# hand_rev_1_0.net
KiCad netlist of a schematic drawn in EAGLE
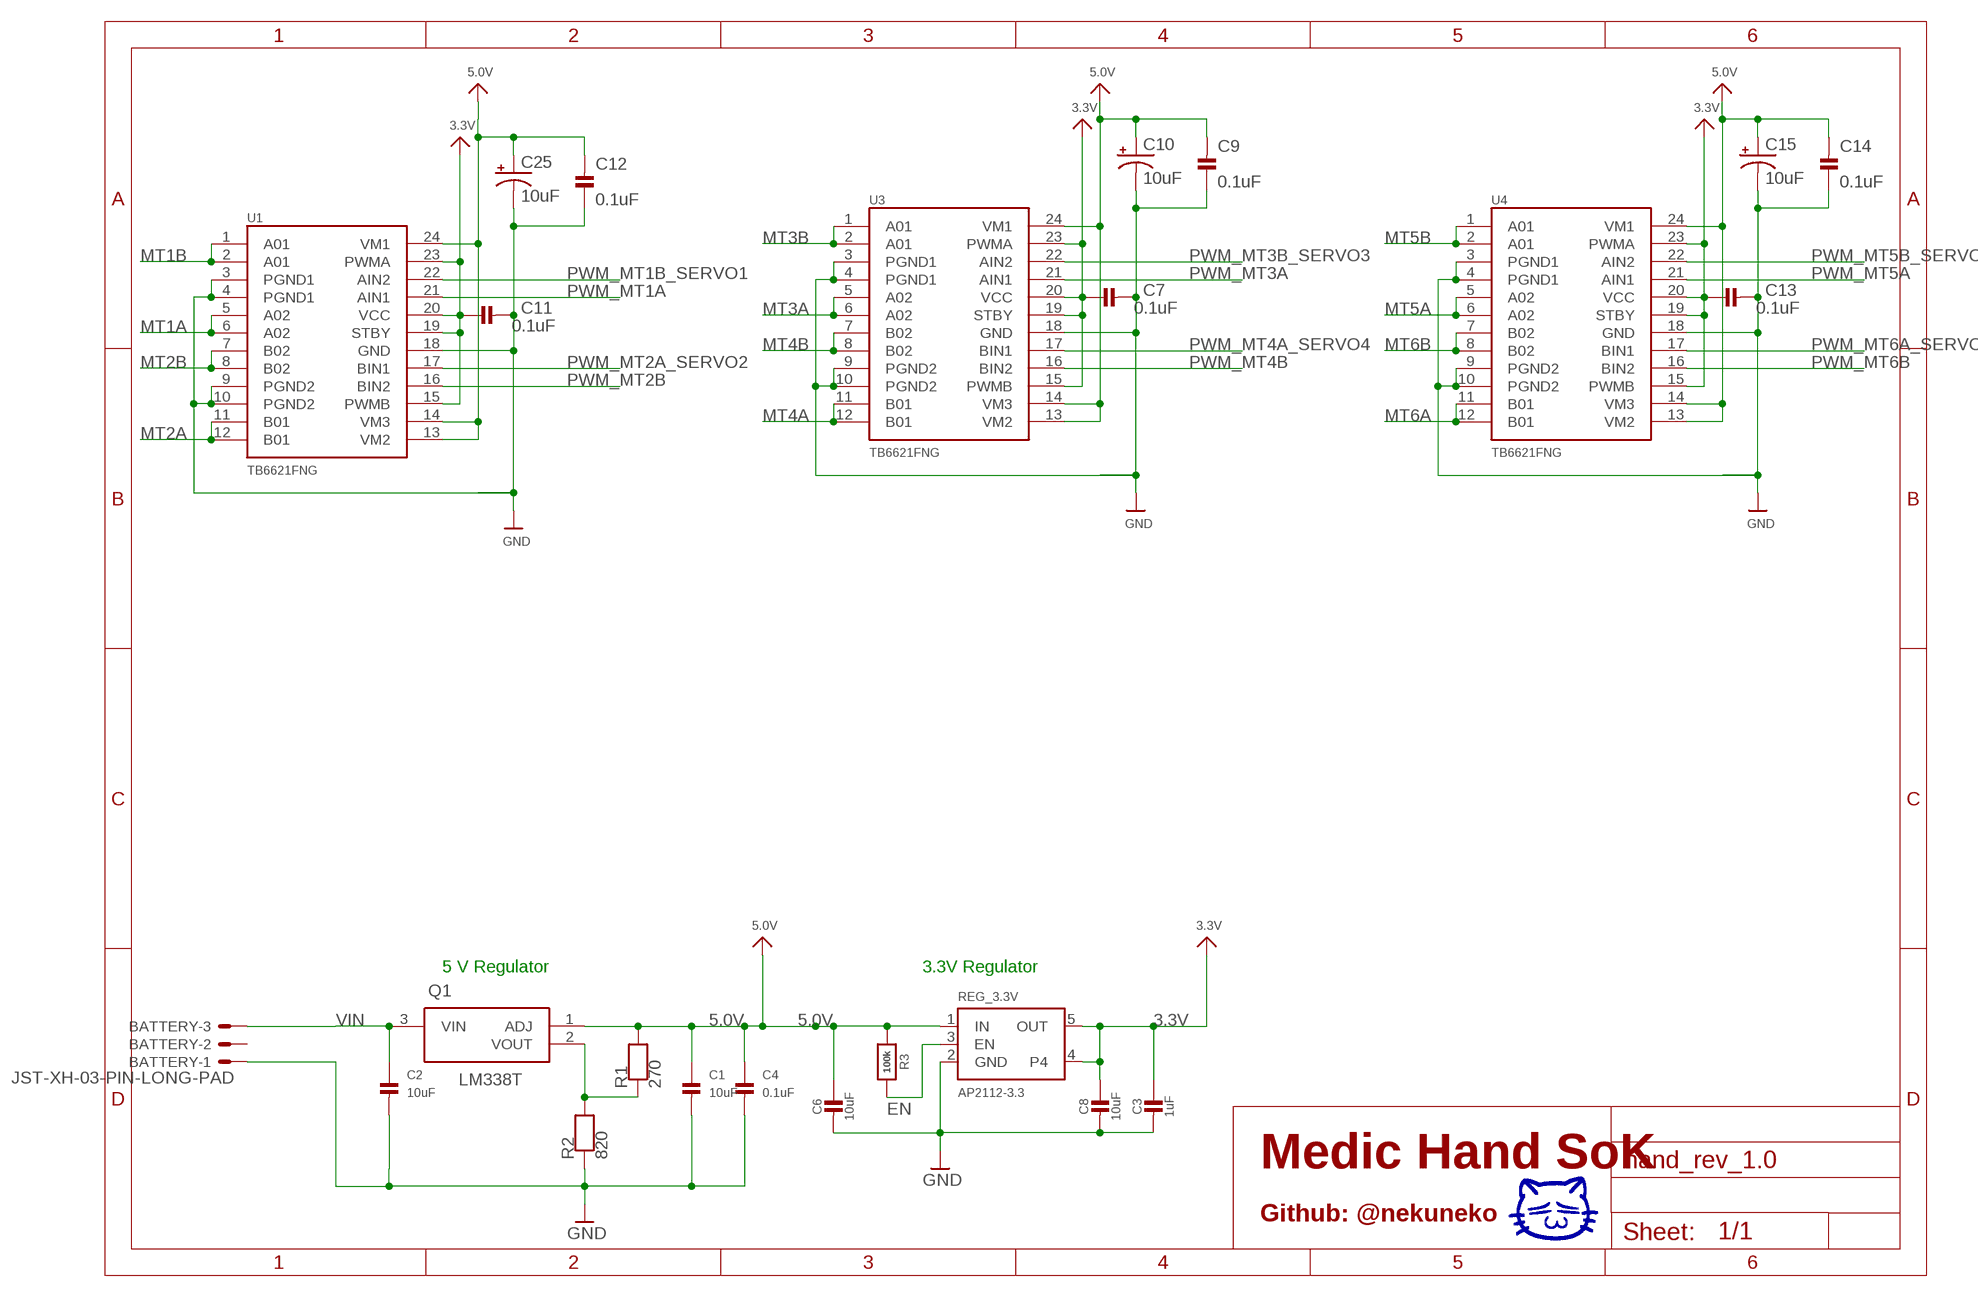
[diagram p0: schematic, sheet 1, part 1 of 2]
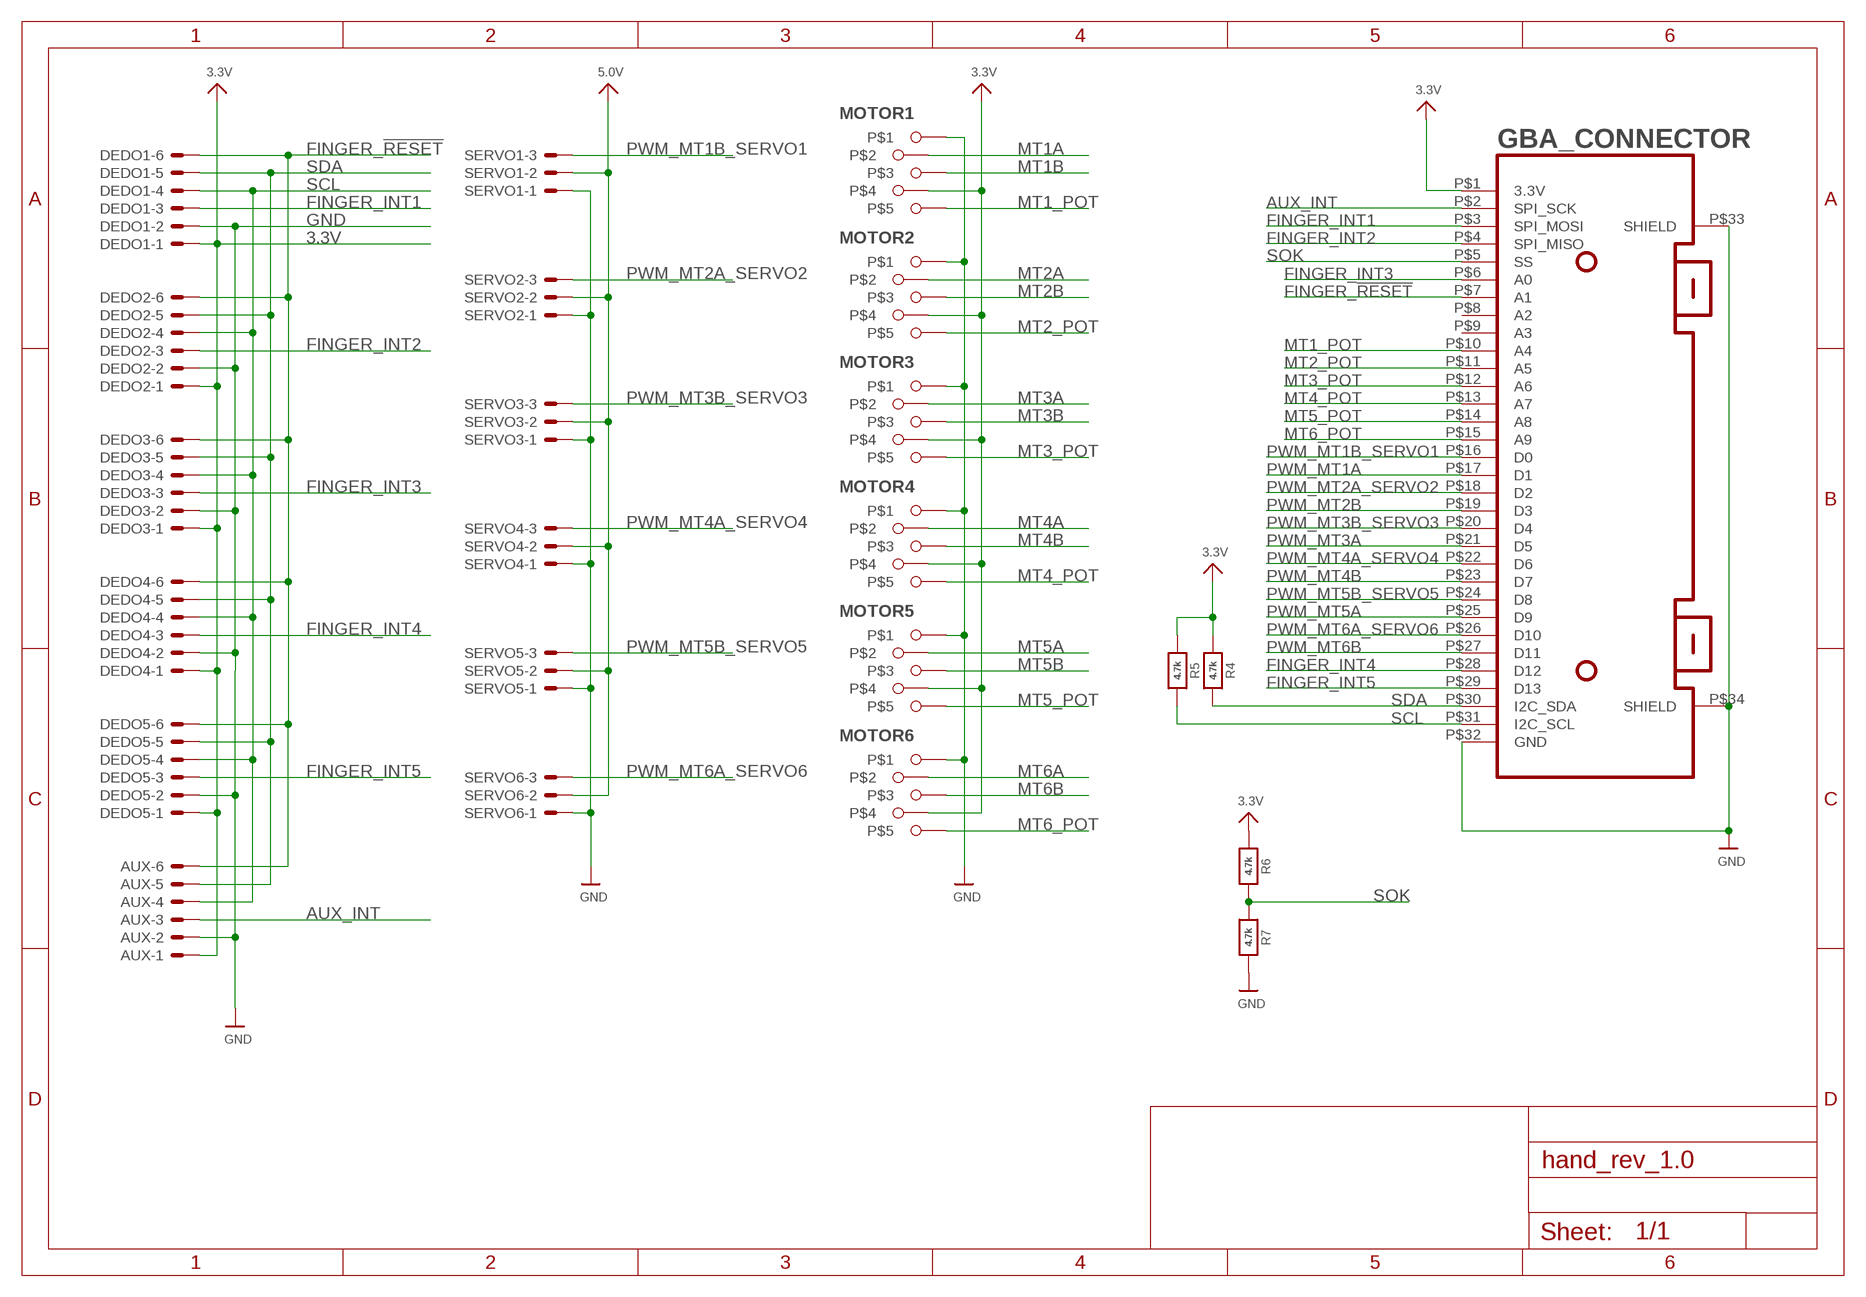
[diagram p1: schematic, sheet 1, part 2 of 2]

(export (version "E")
  (design (tool "Eeschema 10.0.6"))
  (components
    (comp (ref "AUX")
      (value "FINGER_5")
      (footprint "eagle-import:BM06B-SRSS-TB")
      (libsource (lib "eagle-import") (part "?M06B-SRSS-TBB"))
    )
    (comp (ref "BATTERY")
      (value "JST-XH-03-PIN-LONG-PAD")
      (footprint "eagle-import:JST-XH-03-PACKAGE-LONG-PAD")
      (libsource (lib "eagle-import") (part "JST-XH-03-PIN-LONG-PAD"))
    )
    (comp (ref "C1")
      (value "10uF")
      (footprint "eagle-import:_0805")
      (libsource (lib "eagle-import") (part "CAP_CERAMIC_0805"))
    )
    (comp (ref "C2")
      (value "10uF")
      (footprint "eagle-import:_0805")
      (libsource (lib "eagle-import") (part "CAP_CERAMIC_0805"))
    )
    (comp (ref "C3")
      (value "1uF")
      (footprint "eagle-import:_0603")
      (libsource (lib "eagle-import") (part "CAP_CERAMIC_0603"))
    )
    (comp (ref "C4")
      (value "0.1uF")
      (footprint "eagle-import:_0805")
      (libsource (lib "eagle-import") (part "CAP_CERAMIC_0805"))
    )
    (comp (ref "C6")
      (value "10uF")
      (footprint "eagle-import:_0603")
      (libsource (lib "eagle-import") (part "CAP_CERAMIC_0603"))
    )
    (comp (ref "C7")
      (value "0.1uF")
      (footprint "eagle-import:_0603")
      (libsource (lib "eagle-import") (part "CAP_CERAMIC_0603"))
    )
    (comp (ref "C8")
      (value "10uF")
      (footprint "eagle-import:_0603")
      (libsource (lib "eagle-import") (part "CAP_CERAMIC_0603"))
    )
    (comp (ref "C9")
      (value "0.1uF")
      (footprint "eagle-import:_0603")
      (libsource (lib "eagle-import") (part "CAP_CERAMIC_0603"))
    )
    (comp (ref "C10")
      (value "10uF")
      (footprint "eagle-import:0603-POLAR")
      (fields (field (name "MPN") "F981A106MMA"))
      (libsource (lib "eagle-import") (part "10UF-POLAR-0603-6.3V-20%(TANT)"))
    )
    (comp (ref "C11")
      (value "0.1uF")
      (footprint "eagle-import:_0603")
      (libsource (lib "eagle-import") (part "CAP_CERAMIC_0603"))
    )
    (comp (ref "C12")
      (value "0.1uF")
      (footprint "eagle-import:_0603")
      (libsource (lib "eagle-import") (part "CAP_CERAMIC_0603"))
    )
    (comp (ref "C13")
      (value "0.1uF")
      (footprint "eagle-import:_0603")
      (libsource (lib "eagle-import") (part "CAP_CERAMIC_0603"))
    )
    (comp (ref "C14")
      (value "0.1uF")
      (footprint "eagle-import:_0603")
      (libsource (lib "eagle-import") (part "CAP_CERAMIC_0603"))
    )
    (comp (ref "C15")
      (value "10uF")
      (footprint "eagle-import:0603-POLAR")
      (fields (field (name "MPN") "F981A106MMA"))
      (libsource (lib "eagle-import") (part "10UF-POLAR-0603-6.3V-20%(TANT)"))
    )
    (comp (ref "C25")
      (value "10uF")
      (footprint "eagle-import:0603-POLAR")
      (fields (field (name "MPN") "F981A106MMA"))
      (libsource (lib "eagle-import") (part "10UF-POLAR-0603-6.3V-20%(TANT)"))
    )
    (comp (ref "DEDO1")
      (value "FINGER_1")
      (footprint "eagle-import:BM06B-SRSS-TB")
      (libsource (lib "eagle-import") (part "?M06B-SRSS-TBB"))
    )
    (comp (ref "DEDO2")
      (value "FINGER_2")
      (footprint "eagle-import:BM06B-SRSS-TB")
      (libsource (lib "eagle-import") (part "?M06B-SRSS-TBB"))
    )
    (comp (ref "DEDO3")
      (value "FINGER_3")
      (footprint "eagle-import:BM06B-SRSS-TB")
      (libsource (lib "eagle-import") (part "?M06B-SRSS-TBB"))
    )
    (comp (ref "DEDO4")
      (value "FINGER_4")
      (footprint "eagle-import:BM06B-SRSS-TB")
      (libsource (lib "eagle-import") (part "?M06B-SRSS-TBB"))
    )
    (comp (ref "DEDO5")
      (value "FINGER_5")
      (footprint "eagle-import:BM06B-SRSS-TB")
      (libsource (lib "eagle-import") (part "?M06B-SRSS-TBB"))
    )
    (comp (ref "GBA_CONNECTOR")
      (value "GBA_CARTRIDGE")
      (footprint "eagle-import:GBA_CARTRIDGE")
      (libsource (lib "eagle-import") (part "GBA_CARTRIDGE"))
    )
    (comp (ref "MOTOR1")
      (value "MOTOR1")
      (footprint "eagle-import:5PIN")
      (libsource (lib "eagle-import") (part "5PIN"))
    )
    (comp (ref "MOTOR2")
      (value "MOTOR2")
      (footprint "eagle-import:5PIN")
      (libsource (lib "eagle-import") (part "5PIN"))
    )
    (comp (ref "MOTOR3")
      (value "MOTOR3")
      (footprint "eagle-import:5PIN")
      (libsource (lib "eagle-import") (part "5PIN"))
    )
    (comp (ref "MOTOR4")
      (value "MOTOR4")
      (footprint "eagle-import:5PIN")
      (libsource (lib "eagle-import") (part "5PIN"))
    )
    (comp (ref "MOTOR5")
      (value "MOTOR5")
      (footprint "eagle-import:5PIN")
      (libsource (lib "eagle-import") (part "5PIN"))
    )
    (comp (ref "MOTOR6")
      (value "MOTOR6")
      (footprint "eagle-import:5PIN")
      (libsource (lib "eagle-import") (part "5PIN"))
    )
    (comp (ref "Q1")
      (value "LM338T")
      (footprint "eagle-import:TO220")
      (libsource (lib "eagle-import") (part "LM338T"))
    )
    (comp (ref "R1")
      (value "270")
      (footprint "eagle-import:_0805")
      (libsource (lib "eagle-import") (part "RESISTOR_0805"))
    )
    (comp (ref "R2")
      (value "820")
      (footprint "eagle-import:_0805")
      (libsource (lib "eagle-import") (part "RESISTOR_0805"))
    )
    (comp (ref "R3")
      (value "100k")
      (footprint "eagle-import:_0603")
      (libsource (lib "eagle-import") (part "RESISTOR_0603"))
    )
    (comp (ref "R4")
      (value "4.7k")
      (footprint "eagle-import:_0603")
      (libsource (lib "eagle-import") (part "RESISTOR_0603"))
    )
    (comp (ref "R5")
      (value "4.7k")
      (footprint "eagle-import:_0603")
      (libsource (lib "eagle-import") (part "RESISTOR_0603"))
    )
    (comp (ref "R6")
      (value "4.7k")
      (footprint "eagle-import:_0603")
      (libsource (lib "eagle-import") (part "RESISTOR_0603"))
    )
    (comp (ref "R7")
      (value "4.7k")
      (footprint "eagle-import:_0603")
      (libsource (lib "eagle-import") (part "RESISTOR_0603"))
    )
    (comp (ref "REG_3.3V")
      (value "AP2112-3.3")
      (footprint "eagle-import:SOT23-5")
      (libsource (lib "eagle-import") (part "VREG_SOT23-5"))
    )
    (comp (ref "SERVO1")
      (value "JST-XH-03-PIN-LONG-PAD")
      (footprint "eagle-import:JST-XH-03-PACKAGE-LONG-PAD")
      (libsource (lib "eagle-import") (part "JST-XH-03-PIN-LONG-PAD"))
    )
    (comp (ref "SERVO2")
      (value "JST-XH-03-PIN-LONG-PAD")
      (footprint "eagle-import:JST-XH-03-PACKAGE-LONG-PAD")
      (libsource (lib "eagle-import") (part "JST-XH-03-PIN-LONG-PAD"))
    )
    (comp (ref "SERVO3")
      (value "JST-XH-03-PIN-LONG-PAD")
      (footprint "eagle-import:JST-XH-03-PACKAGE-LONG-PAD")
      (libsource (lib "eagle-import") (part "JST-XH-03-PIN-LONG-PAD"))
    )
    (comp (ref "SERVO4")
      (value "JST-XH-03-PIN-LONG-PAD")
      (footprint "eagle-import:JST-XH-03-PACKAGE-LONG-PAD")
      (libsource (lib "eagle-import") (part "JST-XH-03-PIN-LONG-PAD"))
    )
    (comp (ref "SERVO5")
      (value "JST-XH-03-PIN-LONG-PAD")
      (footprint "eagle-import:JST-XH-03-PACKAGE-LONG-PAD")
      (libsource (lib "eagle-import") (part "JST-XH-03-PIN-LONG-PAD"))
    )
    (comp (ref "SERVO6")
      (value "JST-XH-03-PIN-LONG-PAD")
      (footprint "eagle-import:JST-XH-03-PACKAGE-LONG-PAD")
      (libsource (lib "eagle-import") (part "JST-XH-03-PIN-LONG-PAD"))
    )
    (comp (ref "U1")
      (value "TB6621FNG")
      (footprint "eagle-import:SSOP24")
      (libsource (lib "eagle-import") (part "TB6621FNG"))
    )
    (comp (ref "U3")
      (value "TB6621FNG")
      (footprint "eagle-import:SSOP24")
      (libsource (lib "eagle-import") (part "TB6621FNG"))
    )
    (comp (ref "U4")
      (value "TB6621FNG")
      (footprint "eagle-import:SSOP24")
      (libsource (lib "eagle-import") (part "TB6621FNG"))
    )
  )
  (nets
    (net (code "1") (name "/AUX_INT") (class "Default")
      (node (ref "AUX") (pin "3") (pinfunction "S_3") (pintype "passive"))
      (node (ref "GBA_CONNECTOR") (pin "P$2") (pinfunction "SPI_SCK_P$2") (pintype "bidirectional"))
    )
    (net (code "2") (name "/EN") (class "Default")
      (node (ref "R3") (pin "2") (pinfunction "2_2") (pintype "passive"))
      (node (ref "REG_3.3V") (pin "3") (pinfunction "EN_3") (pintype "bidirectional"))
    )
    (net (code "3") (name "/FINGER_INT1") (class "Default")
      (node (ref "DEDO1") (pin "3") (pinfunction "S_3") (pintype "passive"))
      (node (ref "GBA_CONNECTOR") (pin "P$3") (pinfunction "SPI_MOSI_P$3") (pintype "bidirectional"))
    )
    (net (code "4") (name "/FINGER_INT2") (class "Default")
      (node (ref "DEDO2") (pin "3") (pinfunction "S_3") (pintype "passive"))
      (node (ref "GBA_CONNECTOR") (pin "P$4") (pinfunction "SPI_MISO_P$4") (pintype "bidirectional"))
    )
    (net (code "5") (name "/FINGER_INT3") (class "Default")
      (node (ref "DEDO3") (pin "3") (pinfunction "S_3") (pintype "passive"))
      (node (ref "GBA_CONNECTOR") (pin "P$6") (pinfunction "A0_P$6") (pintype "bidirectional"))
    )
    (net (code "6") (name "/FINGER_INT4") (class "Default")
      (node (ref "DEDO4") (pin "3") (pinfunction "S_3") (pintype "passive"))
      (node (ref "GBA_CONNECTOR") (pin "P$28") (pinfunction "D12_P$28") (pintype "bidirectional"))
    )
    (net (code "7") (name "/FINGER_INT5") (class "Default")
      (node (ref "DEDO5") (pin "3") (pinfunction "S_3") (pintype "passive"))
      (node (ref "GBA_CONNECTOR") (pin "P$29") (pinfunction "D13_P$29") (pintype "bidirectional"))
    )
    (net (code "8") (name "/FINGER_~{RESET}") (class "Default")
      (node (ref "AUX") (pin "6") (pinfunction "S_6") (pintype "passive"))
      (node (ref "DEDO1") (pin "6") (pinfunction "S_6") (pintype "passive"))
      (node (ref "DEDO2") (pin "6") (pinfunction "S_6") (pintype "passive"))
      (node (ref "DEDO3") (pin "6") (pinfunction "S_6") (pintype "passive"))
      (node (ref "DEDO4") (pin "6") (pinfunction "S_6") (pintype "passive"))
      (node (ref "DEDO5") (pin "6") (pinfunction "S_6") (pintype "passive"))
      (node (ref "GBA_CONNECTOR") (pin "P$7") (pinfunction "A1_P$7") (pintype "bidirectional"))
    )
    (net (code "9") (name "/MT1A") (class "Default")
      (node (ref "MOTOR1") (pin "2") (pinfunction "P$2_2") (pintype "bidirectional"))
      (node (ref "U1") (pin "5") (pinfunction "A02_5") (pintype "bidirectional"))
      (node (ref "U1") (pin "6") (pinfunction "A02_6") (pintype "bidirectional"))
    )
    (net (code "10") (name "/MT1B") (class "Default")
      (node (ref "MOTOR1") (pin "3") (pinfunction "P$3_3") (pintype "bidirectional"))
      (node (ref "U1") (pin "1") (pinfunction "A01_1") (pintype "bidirectional"))
      (node (ref "U1") (pin "2") (pinfunction "A01_2") (pintype "bidirectional"))
    )
    (net (code "11") (name "/MT1_POT") (class "Default")
      (node (ref "GBA_CONNECTOR") (pin "P$10") (pinfunction "A4_P$10") (pintype "bidirectional"))
      (node (ref "MOTOR1") (pin "5") (pinfunction "P$5_5") (pintype "bidirectional"))
    )
    (net (code "12") (name "/MT2A") (class "Default")
      (node (ref "MOTOR2") (pin "2") (pinfunction "P$2_2") (pintype "bidirectional"))
      (node (ref "U1") (pin "11") (pinfunction "B01_11") (pintype "bidirectional"))
      (node (ref "U1") (pin "12") (pinfunction "B01_12") (pintype "bidirectional"))
    )
    (net (code "13") (name "/MT2B") (class "Default")
      (node (ref "MOTOR2") (pin "3") (pinfunction "P$3_3") (pintype "bidirectional"))
      (node (ref "U1") (pin "7") (pinfunction "B02_7") (pintype "bidirectional"))
      (node (ref "U1") (pin "8") (pinfunction "B02_8") (pintype "bidirectional"))
    )
    (net (code "14") (name "/MT2_POT") (class "Default")
      (node (ref "GBA_CONNECTOR") (pin "P$11") (pinfunction "A5_P$11") (pintype "bidirectional"))
      (node (ref "MOTOR2") (pin "5") (pinfunction "P$5_5") (pintype "bidirectional"))
    )
    (net (code "15") (name "/MT3A") (class "Default")
      (node (ref "MOTOR3") (pin "2") (pinfunction "P$2_2") (pintype "bidirectional"))
      (node (ref "U3") (pin "5") (pinfunction "A02_5") (pintype "bidirectional"))
      (node (ref "U3") (pin "6") (pinfunction "A02_6") (pintype "bidirectional"))
    )
    (net (code "16") (name "/MT3B") (class "Default")
      (node (ref "MOTOR3") (pin "3") (pinfunction "P$3_3") (pintype "bidirectional"))
      (node (ref "U3") (pin "1") (pinfunction "A01_1") (pintype "bidirectional"))
      (node (ref "U3") (pin "2") (pinfunction "A01_2") (pintype "bidirectional"))
    )
    (net (code "17") (name "/MT3_POT") (class "Default")
      (node (ref "GBA_CONNECTOR") (pin "P$12") (pinfunction "A6_P$12") (pintype "bidirectional"))
      (node (ref "MOTOR3") (pin "5") (pinfunction "P$5_5") (pintype "bidirectional"))
    )
    (net (code "18") (name "/MT4A") (class "Default")
      (node (ref "MOTOR4") (pin "2") (pinfunction "P$2_2") (pintype "bidirectional"))
      (node (ref "U3") (pin "11") (pinfunction "B01_11") (pintype "bidirectional"))
      (node (ref "U3") (pin "12") (pinfunction "B01_12") (pintype "bidirectional"))
    )
    (net (code "19") (name "/MT4B") (class "Default")
      (node (ref "MOTOR4") (pin "3") (pinfunction "P$3_3") (pintype "bidirectional"))
      (node (ref "U3") (pin "7") (pinfunction "B02_7") (pintype "bidirectional"))
      (node (ref "U3") (pin "8") (pinfunction "B02_8") (pintype "bidirectional"))
    )
    (net (code "20") (name "/MT4_POT") (class "Default")
      (node (ref "GBA_CONNECTOR") (pin "P$13") (pinfunction "A7_P$13") (pintype "bidirectional"))
      (node (ref "MOTOR4") (pin "5") (pinfunction "P$5_5") (pintype "bidirectional"))
    )
    (net (code "21") (name "/MT5A") (class "Default")
      (node (ref "MOTOR5") (pin "2") (pinfunction "P$2_2") (pintype "bidirectional"))
      (node (ref "U4") (pin "5") (pinfunction "A02_5") (pintype "bidirectional"))
      (node (ref "U4") (pin "6") (pinfunction "A02_6") (pintype "bidirectional"))
    )
    (net (code "22") (name "/MT5B") (class "Default")
      (node (ref "MOTOR5") (pin "3") (pinfunction "P$3_3") (pintype "bidirectional"))
      (node (ref "U4") (pin "1") (pinfunction "A01_1") (pintype "bidirectional"))
      (node (ref "U4") (pin "2") (pinfunction "A01_2") (pintype "bidirectional"))
    )
    (net (code "23") (name "/MT5_POT") (class "Default")
      (node (ref "GBA_CONNECTOR") (pin "P$14") (pinfunction "A8_P$14") (pintype "bidirectional"))
      (node (ref "MOTOR5") (pin "5") (pinfunction "P$5_5") (pintype "bidirectional"))
    )
    (net (code "24") (name "/MT6A") (class "Default")
      (node (ref "MOTOR6") (pin "2") (pinfunction "P$2_2") (pintype "bidirectional"))
      (node (ref "U4") (pin "11") (pinfunction "B01_11") (pintype "bidirectional"))
      (node (ref "U4") (pin "12") (pinfunction "B01_12") (pintype "bidirectional"))
    )
    (net (code "25") (name "/MT6B") (class "Default")
      (node (ref "MOTOR6") (pin "3") (pinfunction "P$3_3") (pintype "bidirectional"))
      (node (ref "U4") (pin "7") (pinfunction "B02_7") (pintype "bidirectional"))
      (node (ref "U4") (pin "8") (pinfunction "B02_8") (pintype "bidirectional"))
    )
    (net (code "26") (name "/MT6_POT") (class "Default")
      (node (ref "GBA_CONNECTOR") (pin "P$15") (pinfunction "A9_P$15") (pintype "bidirectional"))
      (node (ref "MOTOR6") (pin "5") (pinfunction "P$5_5") (pintype "bidirectional"))
    )
    (net (code "27") (name "/PWM_MT1A") (class "Default")
      (node (ref "GBA_CONNECTOR") (pin "P$17") (pinfunction "D1_P$17") (pintype "bidirectional"))
      (node (ref "U1") (pin "21") (pinfunction "AIN1_21") (pintype "bidirectional"))
    )
    (net (code "28") (name "/PWM_MT1B_SERVO1") (class "Default")
      (node (ref "GBA_CONNECTOR") (pin "P$16") (pinfunction "D0_P$16") (pintype "bidirectional"))
      (node (ref "SERVO1") (pin "3") (pinfunction "S_3") (pintype "passive"))
      (node (ref "U1") (pin "22") (pinfunction "AIN2_22") (pintype "bidirectional"))
    )
    (net (code "29") (name "/PWM_MT2A_SERVO2") (class "Default")
      (node (ref "GBA_CONNECTOR") (pin "P$18") (pinfunction "D2_P$18") (pintype "bidirectional"))
      (node (ref "SERVO2") (pin "3") (pinfunction "S_3") (pintype "passive"))
      (node (ref "U1") (pin "17") (pinfunction "BIN1_17") (pintype "bidirectional"))
    )
    (net (code "30") (name "/PWM_MT2B") (class "Default")
      (node (ref "GBA_CONNECTOR") (pin "P$19") (pinfunction "D3_P$19") (pintype "bidirectional"))
      (node (ref "U1") (pin "16") (pinfunction "BIN2_16") (pintype "bidirectional"))
    )
    (net (code "31") (name "/PWM_MT3A") (class "Default")
      (node (ref "GBA_CONNECTOR") (pin "P$21") (pinfunction "D5_P$21") (pintype "bidirectional"))
      (node (ref "U3") (pin "21") (pinfunction "AIN1_21") (pintype "bidirectional"))
    )
    (net (code "32") (name "/PWM_MT3B_SERVO3") (class "Default")
      (node (ref "GBA_CONNECTOR") (pin "P$20") (pinfunction "D4_P$20") (pintype "bidirectional"))
      (node (ref "SERVO3") (pin "3") (pinfunction "S_3") (pintype "passive"))
      (node (ref "U3") (pin "22") (pinfunction "AIN2_22") (pintype "bidirectional"))
    )
    (net (code "33") (name "/PWM_MT4A_SERVO4") (class "Default")
      (node (ref "GBA_CONNECTOR") (pin "P$22") (pinfunction "D6_P$22") (pintype "bidirectional"))
      (node (ref "SERVO4") (pin "3") (pinfunction "S_3") (pintype "passive"))
      (node (ref "U3") (pin "17") (pinfunction "BIN1_17") (pintype "bidirectional"))
    )
    (net (code "34") (name "/PWM_MT4B") (class "Default")
      (node (ref "GBA_CONNECTOR") (pin "P$23") (pinfunction "D7_P$23") (pintype "bidirectional"))
      (node (ref "U3") (pin "16") (pinfunction "BIN2_16") (pintype "bidirectional"))
    )
    (net (code "35") (name "/PWM_MT5A") (class "Default")
      (node (ref "GBA_CONNECTOR") (pin "P$25") (pinfunction "D9_P$25") (pintype "bidirectional"))
      (node (ref "U4") (pin "21") (pinfunction "AIN1_21") (pintype "bidirectional"))
    )
    (net (code "36") (name "/PWM_MT5B_SERVO5") (class "Default")
      (node (ref "GBA_CONNECTOR") (pin "P$24") (pinfunction "D8_P$24") (pintype "bidirectional"))
      (node (ref "SERVO5") (pin "3") (pinfunction "S_3") (pintype "passive"))
      (node (ref "U4") (pin "22") (pinfunction "AIN2_22") (pintype "bidirectional"))
    )
    (net (code "37") (name "/PWM_MT6A_SERVO6") (class "Default")
      (node (ref "GBA_CONNECTOR") (pin "P$26") (pinfunction "D10_P$26") (pintype "bidirectional"))
      (node (ref "SERVO6") (pin "3") (pinfunction "S_3") (pintype "passive"))
      (node (ref "U4") (pin "17") (pinfunction "BIN1_17") (pintype "bidirectional"))
    )
    (net (code "38") (name "/PWM_MT6B") (class "Default")
      (node (ref "GBA_CONNECTOR") (pin "P$27") (pinfunction "D11_P$27") (pintype "bidirectional"))
      (node (ref "U4") (pin "16") (pinfunction "BIN2_16") (pintype "bidirectional"))
    )
    (net (code "39") (name "/SCL") (class "Default")
      (node (ref "AUX") (pin "4") (pinfunction "S_4") (pintype "passive"))
      (node (ref "DEDO1") (pin "4") (pinfunction "S_4") (pintype "passive"))
      (node (ref "DEDO2") (pin "4") (pinfunction "S_4") (pintype "passive"))
      (node (ref "DEDO3") (pin "4") (pinfunction "S_4") (pintype "passive"))
      (node (ref "DEDO4") (pin "4") (pinfunction "S_4") (pintype "passive"))
      (node (ref "DEDO5") (pin "4") (pinfunction "S_4") (pintype "passive"))
      (node (ref "GBA_CONNECTOR") (pin "P$31") (pinfunction "I2C_SCL_P$31") (pintype "bidirectional"))
      (node (ref "R5") (pin "2") (pinfunction "2_2") (pintype "passive"))
    )
    (net (code "40") (name "/SDA") (class "Default")
      (node (ref "AUX") (pin "5") (pinfunction "S_5") (pintype "passive"))
      (node (ref "DEDO1") (pin "5") (pinfunction "S_5") (pintype "passive"))
      (node (ref "DEDO2") (pin "5") (pinfunction "S_5") (pintype "passive"))
      (node (ref "DEDO3") (pin "5") (pinfunction "S_5") (pintype "passive"))
      (node (ref "DEDO4") (pin "5") (pinfunction "S_5") (pintype "passive"))
      (node (ref "DEDO5") (pin "5") (pinfunction "S_5") (pintype "passive"))
      (node (ref "GBA_CONNECTOR") (pin "P$30") (pinfunction "I2C_SDA_P$30") (pintype "bidirectional"))
      (node (ref "R4") (pin "2") (pinfunction "2_2") (pintype "passive"))
    )
    (net (code "41") (name "/SOK") (class "Default")
      (node (ref "GBA_CONNECTOR") (pin "P$5") (pinfunction "SS_P$5") (pintype "bidirectional"))
      (node (ref "R6") (pin "2") (pinfunction "2_2") (pintype "passive"))
      (node (ref "R7") (pin "1") (pinfunction "1_1") (pintype "passive"))
    )
    (net (code "42") (name "/VIN") (class "Default")
      (node (ref "BATTERY") (pin "3") (pinfunction "S_3") (pintype "passive"))
      (node (ref "C2") (pin "1") (pinfunction "P$1_1") (pintype "passive"))
      (node (ref "Q1") (pin "3") (pinfunction "VIN_3") (pintype "power_in"))
    )
    (net (code "43") (name "3.3V") (class "Default")
      (node (ref "AUX") (pin "1") (pinfunction "S_1") (pintype "passive"))
      (node (ref "C11") (pin "1") (pinfunction "P$1_1") (pintype "passive"))
      (node (ref "C13") (pin "1") (pinfunction "P$1_1") (pintype "passive"))
      (node (ref "C3") (pin "1") (pinfunction "P$1_1") (pintype "passive"))
      (node (ref "C7") (pin "1") (pinfunction "P$1_1") (pintype "passive"))
      (node (ref "C8") (pin "1") (pinfunction "P$1_1") (pintype "passive"))
      (node (ref "DEDO1") (pin "1") (pinfunction "S_1") (pintype "passive"))
      (node (ref "DEDO2") (pin "1") (pinfunction "S_1") (pintype "passive"))
      (node (ref "DEDO3") (pin "1") (pinfunction "S_1") (pintype "passive"))
      (node (ref "DEDO4") (pin "1") (pinfunction "S_1") (pintype "passive"))
      (node (ref "DEDO5") (pin "1") (pinfunction "S_1") (pintype "passive"))
      (node (ref "GBA_CONNECTOR") (pin "P$1") (pinfunction "3.3V_P$1") (pintype "power_in"))
      (node (ref "MOTOR1") (pin "4") (pinfunction "P$4_4") (pintype "bidirectional"))
      (node (ref "MOTOR2") (pin "4") (pinfunction "P$4_4") (pintype "bidirectional"))
      (node (ref "MOTOR3") (pin "4") (pinfunction "P$4_4") (pintype "bidirectional"))
      (node (ref "MOTOR4") (pin "4") (pinfunction "P$4_4") (pintype "bidirectional"))
      (node (ref "MOTOR5") (pin "4") (pinfunction "P$4_4") (pintype "bidirectional"))
      (node (ref "MOTOR6") (pin "4") (pinfunction "P$4_4") (pintype "bidirectional"))
      (node (ref "R4") (pin "1") (pinfunction "1_1") (pintype "passive"))
      (node (ref "R5") (pin "1") (pinfunction "1_1") (pintype "passive"))
      (node (ref "R6") (pin "1") (pinfunction "1_1") (pintype "passive"))
      (node (ref "REG_3.3V") (pin "4") (pinfunction "P4_4") (pintype "bidirectional"))
      (node (ref "REG_3.3V") (pin "5") (pinfunction "OUT_5") (pintype "bidirectional"))
      (node (ref "U1") (pin "15") (pinfunction "PWMB_15") (pintype "bidirectional"))
      (node (ref "U1") (pin "19") (pinfunction "STBY_19") (pintype "bidirectional"))
      (node (ref "U1") (pin "20") (pinfunction "VCC_20") (pintype "bidirectional"))
      (node (ref "U1") (pin "23") (pinfunction "PWMA_23") (pintype "bidirectional"))
      (node (ref "U3") (pin "15") (pinfunction "PWMB_15") (pintype "bidirectional"))
      (node (ref "U3") (pin "19") (pinfunction "STBY_19") (pintype "bidirectional"))
      (node (ref "U3") (pin "20") (pinfunction "VCC_20") (pintype "bidirectional"))
      (node (ref "U3") (pin "23") (pinfunction "PWMA_23") (pintype "bidirectional"))
      (node (ref "U4") (pin "15") (pinfunction "PWMB_15") (pintype "bidirectional"))
      (node (ref "U4") (pin "19") (pinfunction "STBY_19") (pintype "bidirectional"))
      (node (ref "U4") (pin "20") (pinfunction "VCC_20") (pintype "bidirectional"))
      (node (ref "U4") (pin "23") (pinfunction "PWMA_23") (pintype "bidirectional"))
    )
    (net (code "44") (name "5.0V") (class "Default")
      (node (ref "C1") (pin "1") (pinfunction "P$1_1") (pintype "passive"))
      (node (ref "C10") (pin "+") (pinfunction "+_+") (pintype "passive"))
      (node (ref "C12") (pin "2") (pinfunction "P$2_2") (pintype "passive"))
      (node (ref "C14") (pin "2") (pinfunction "P$2_2") (pintype "passive"))
      (node (ref "C15") (pin "+") (pinfunction "+_+") (pintype "passive"))
      (node (ref "C25") (pin "+") (pinfunction "+_+") (pintype "passive"))
      (node (ref "C4") (pin "1") (pinfunction "P$1_1") (pintype "passive"))
      (node (ref "C6") (pin "1") (pinfunction "P$1_1") (pintype "passive"))
      (node (ref "C9") (pin "2") (pinfunction "P$2_2") (pintype "passive"))
      (node (ref "Q1") (pin "1") (pinfunction "ADJ_1") (pintype "bidirectional"))
      (node (ref "R1") (pin "2") (pinfunction "2_2") (pintype "passive"))
      (node (ref "R3") (pin "1") (pinfunction "1_1") (pintype "passive"))
      (node (ref "REG_3.3V") (pin "1") (pinfunction "IN_1") (pintype "bidirectional"))
      (node (ref "SERVO1") (pin "2") (pinfunction "S_2") (pintype "passive"))
      (node (ref "SERVO2") (pin "2") (pinfunction "S_2") (pintype "passive"))
      (node (ref "SERVO3") (pin "2") (pinfunction "S_2") (pintype "passive"))
      (node (ref "SERVO4") (pin "2") (pinfunction "S_2") (pintype "passive"))
      (node (ref "SERVO5") (pin "2") (pinfunction "S_2") (pintype "passive"))
      (node (ref "SERVO6") (pin "2") (pinfunction "S_2") (pintype "passive"))
      (node (ref "U1") (pin "13") (pinfunction "VM2_13") (pintype "bidirectional"))
      (node (ref "U1") (pin "14") (pinfunction "VM3_14") (pintype "bidirectional"))
      (node (ref "U1") (pin "24") (pinfunction "VM1_24") (pintype "bidirectional"))
      (node (ref "U3") (pin "13") (pinfunction "VM2_13") (pintype "bidirectional"))
      (node (ref "U3") (pin "14") (pinfunction "VM3_14") (pintype "bidirectional"))
      (node (ref "U3") (pin "24") (pinfunction "VM1_24") (pintype "bidirectional"))
      (node (ref "U4") (pin "13") (pinfunction "VM2_13") (pintype "bidirectional"))
      (node (ref "U4") (pin "14") (pinfunction "VM3_14") (pintype "bidirectional"))
      (node (ref "U4") (pin "24") (pinfunction "VM1_24") (pintype "bidirectional"))
    )
    (net (code "45") (name "GND") (class "Default")
      (node (ref "AUX") (pin "2") (pinfunction "S_2") (pintype "passive"))
      (node (ref "BATTERY") (pin "1") (pinfunction "S_1") (pintype "passive"))
      (node (ref "C1") (pin "2") (pinfunction "P$2_2") (pintype "passive"))
      (node (ref "C10") (pin "-") (pinfunction "-_-") (pintype "passive"))
      (node (ref "C11") (pin "2") (pinfunction "P$2_2") (pintype "passive"))
      (node (ref "C12") (pin "1") (pinfunction "P$1_1") (pintype "passive"))
      (node (ref "C13") (pin "2") (pinfunction "P$2_2") (pintype "passive"))
      (node (ref "C14") (pin "1") (pinfunction "P$1_1") (pintype "passive"))
      (node (ref "C15") (pin "-") (pinfunction "-_-") (pintype "passive"))
      (node (ref "C2") (pin "2") (pinfunction "P$2_2") (pintype "passive"))
      (node (ref "C25") (pin "-") (pinfunction "-_-") (pintype "passive"))
      (node (ref "C3") (pin "2") (pinfunction "P$2_2") (pintype "passive"))
      (node (ref "C4") (pin "2") (pinfunction "P$2_2") (pintype "passive"))
      (node (ref "C6") (pin "2") (pinfunction "P$2_2") (pintype "passive"))
      (node (ref "C7") (pin "2") (pinfunction "P$2_2") (pintype "passive"))
      (node (ref "C8") (pin "2") (pinfunction "P$2_2") (pintype "passive"))
      (node (ref "C9") (pin "1") (pinfunction "P$1_1") (pintype "passive"))
      (node (ref "DEDO1") (pin "2") (pinfunction "S_2") (pintype "passive"))
      (node (ref "DEDO2") (pin "2") (pinfunction "S_2") (pintype "passive"))
      (node (ref "DEDO3") (pin "2") (pinfunction "S_2") (pintype "passive"))
      (node (ref "DEDO4") (pin "2") (pinfunction "S_2") (pintype "passive"))
      (node (ref "DEDO5") (pin "2") (pinfunction "S_2") (pintype "passive"))
      (node (ref "GBA_CONNECTOR") (pin "P$32") (pinfunction "GND_P$32") (pintype "power_in"))
      (node (ref "GBA_CONNECTOR") (pin "P$33") (pinfunction "SHIELD_P$33") (pintype "bidirectional"))
      (node (ref "GBA_CONNECTOR") (pin "P$34") (pinfunction "SHIELD_P$34") (pintype "bidirectional"))
      (node (ref "MOTOR1") (pin "1") (pinfunction "P$1_1") (pintype "bidirectional"))
      (node (ref "MOTOR2") (pin "1") (pinfunction "P$1_1") (pintype "bidirectional"))
      (node (ref "MOTOR3") (pin "1") (pinfunction "P$1_1") (pintype "bidirectional"))
      (node (ref "MOTOR4") (pin "1") (pinfunction "P$1_1") (pintype "bidirectional"))
      (node (ref "MOTOR5") (pin "1") (pinfunction "P$1_1") (pintype "bidirectional"))
      (node (ref "MOTOR6") (pin "1") (pinfunction "P$1_1") (pintype "bidirectional"))
      (node (ref "R2") (pin "1") (pinfunction "1_1") (pintype "passive"))
      (node (ref "R7") (pin "2") (pinfunction "2_2") (pintype "passive"))
      (node (ref "REG_3.3V") (pin "2") (pinfunction "GND_2") (pintype "bidirectional"))
      (node (ref "SERVO1") (pin "1") (pinfunction "S_1") (pintype "passive"))
      (node (ref "SERVO2") (pin "1") (pinfunction "S_1") (pintype "passive"))
      (node (ref "SERVO3") (pin "1") (pinfunction "S_1") (pintype "passive"))
      (node (ref "SERVO4") (pin "1") (pinfunction "S_1") (pintype "passive"))
      (node (ref "SERVO5") (pin "1") (pinfunction "S_1") (pintype "passive"))
      (node (ref "SERVO6") (pin "1") (pinfunction "S_1") (pintype "passive"))
      (node (ref "U1") (pin "10") (pinfunction "PGND2_10") (pintype "bidirectional"))
      (node (ref "U1") (pin "18") (pinfunction "GND_18") (pintype "bidirectional"))
      (node (ref "U1") (pin "3") (pinfunction "PGND1_3") (pintype "bidirectional"))
      (node (ref "U1") (pin "4") (pinfunction "PGND1_4") (pintype "bidirectional"))
      (node (ref "U1") (pin "9") (pinfunction "PGND2_9") (pintype "bidirectional"))
      (node (ref "U3") (pin "10") (pinfunction "PGND2_10") (pintype "bidirectional"))
      (node (ref "U3") (pin "18") (pinfunction "GND_18") (pintype "bidirectional"))
      (node (ref "U3") (pin "3") (pinfunction "PGND1_3") (pintype "bidirectional"))
      (node (ref "U3") (pin "4") (pinfunction "PGND1_4") (pintype "bidirectional"))
      (node (ref "U3") (pin "9") (pinfunction "PGND2_9") (pintype "bidirectional"))
      (node (ref "U4") (pin "10") (pinfunction "PGND2_10") (pintype "bidirectional"))
      (node (ref "U4") (pin "18") (pinfunction "GND_18") (pintype "bidirectional"))
      (node (ref "U4") (pin "3") (pinfunction "PGND1_3") (pintype "bidirectional"))
      (node (ref "U4") (pin "4") (pinfunction "PGND1_4") (pintype "bidirectional"))
      (node (ref "U4") (pin "9") (pinfunction "PGND2_9") (pintype "bidirectional"))
    )
    (net (code "46") (name "Net-(Q1-VOUT)") (class "Default")
      (node (ref "Q1") (pin "2") (pinfunction "VOUT_2") (pintype "power_in"))
      (node (ref "R1") (pin "1") (pinfunction "1_1") (pintype "passive"))
      (node (ref "R2") (pin "2") (pinfunction "2_2") (pintype "passive"))
    )
    (net (code "47") (name "unconnected-(BATTERYB-S-Pad2)") (class "Default")
      (node (ref "BATTERY") (pin "2") (pinfunction "S_2") (pintype "passive"))
    )
    (net (code "48") (name "unconnected-(GBA_CONNECTOR-A2-PadP$8)") (class "Default")
      (node (ref "GBA_CONNECTOR") (pin "P$8") (pinfunction "A2_P$8") (pintype "bidirectional"))
    )
    (net (code "49") (name "unconnected-(GBA_CONNECTOR-A3-PadP$9)") (class "Default")
      (node (ref "GBA_CONNECTOR") (pin "P$9") (pinfunction "A3_P$9") (pintype "bidirectional"))
    )
  )
)
